# k26_baseboard_connectors1.net
KiCad netlist of a schematic drawn in Altium Designer
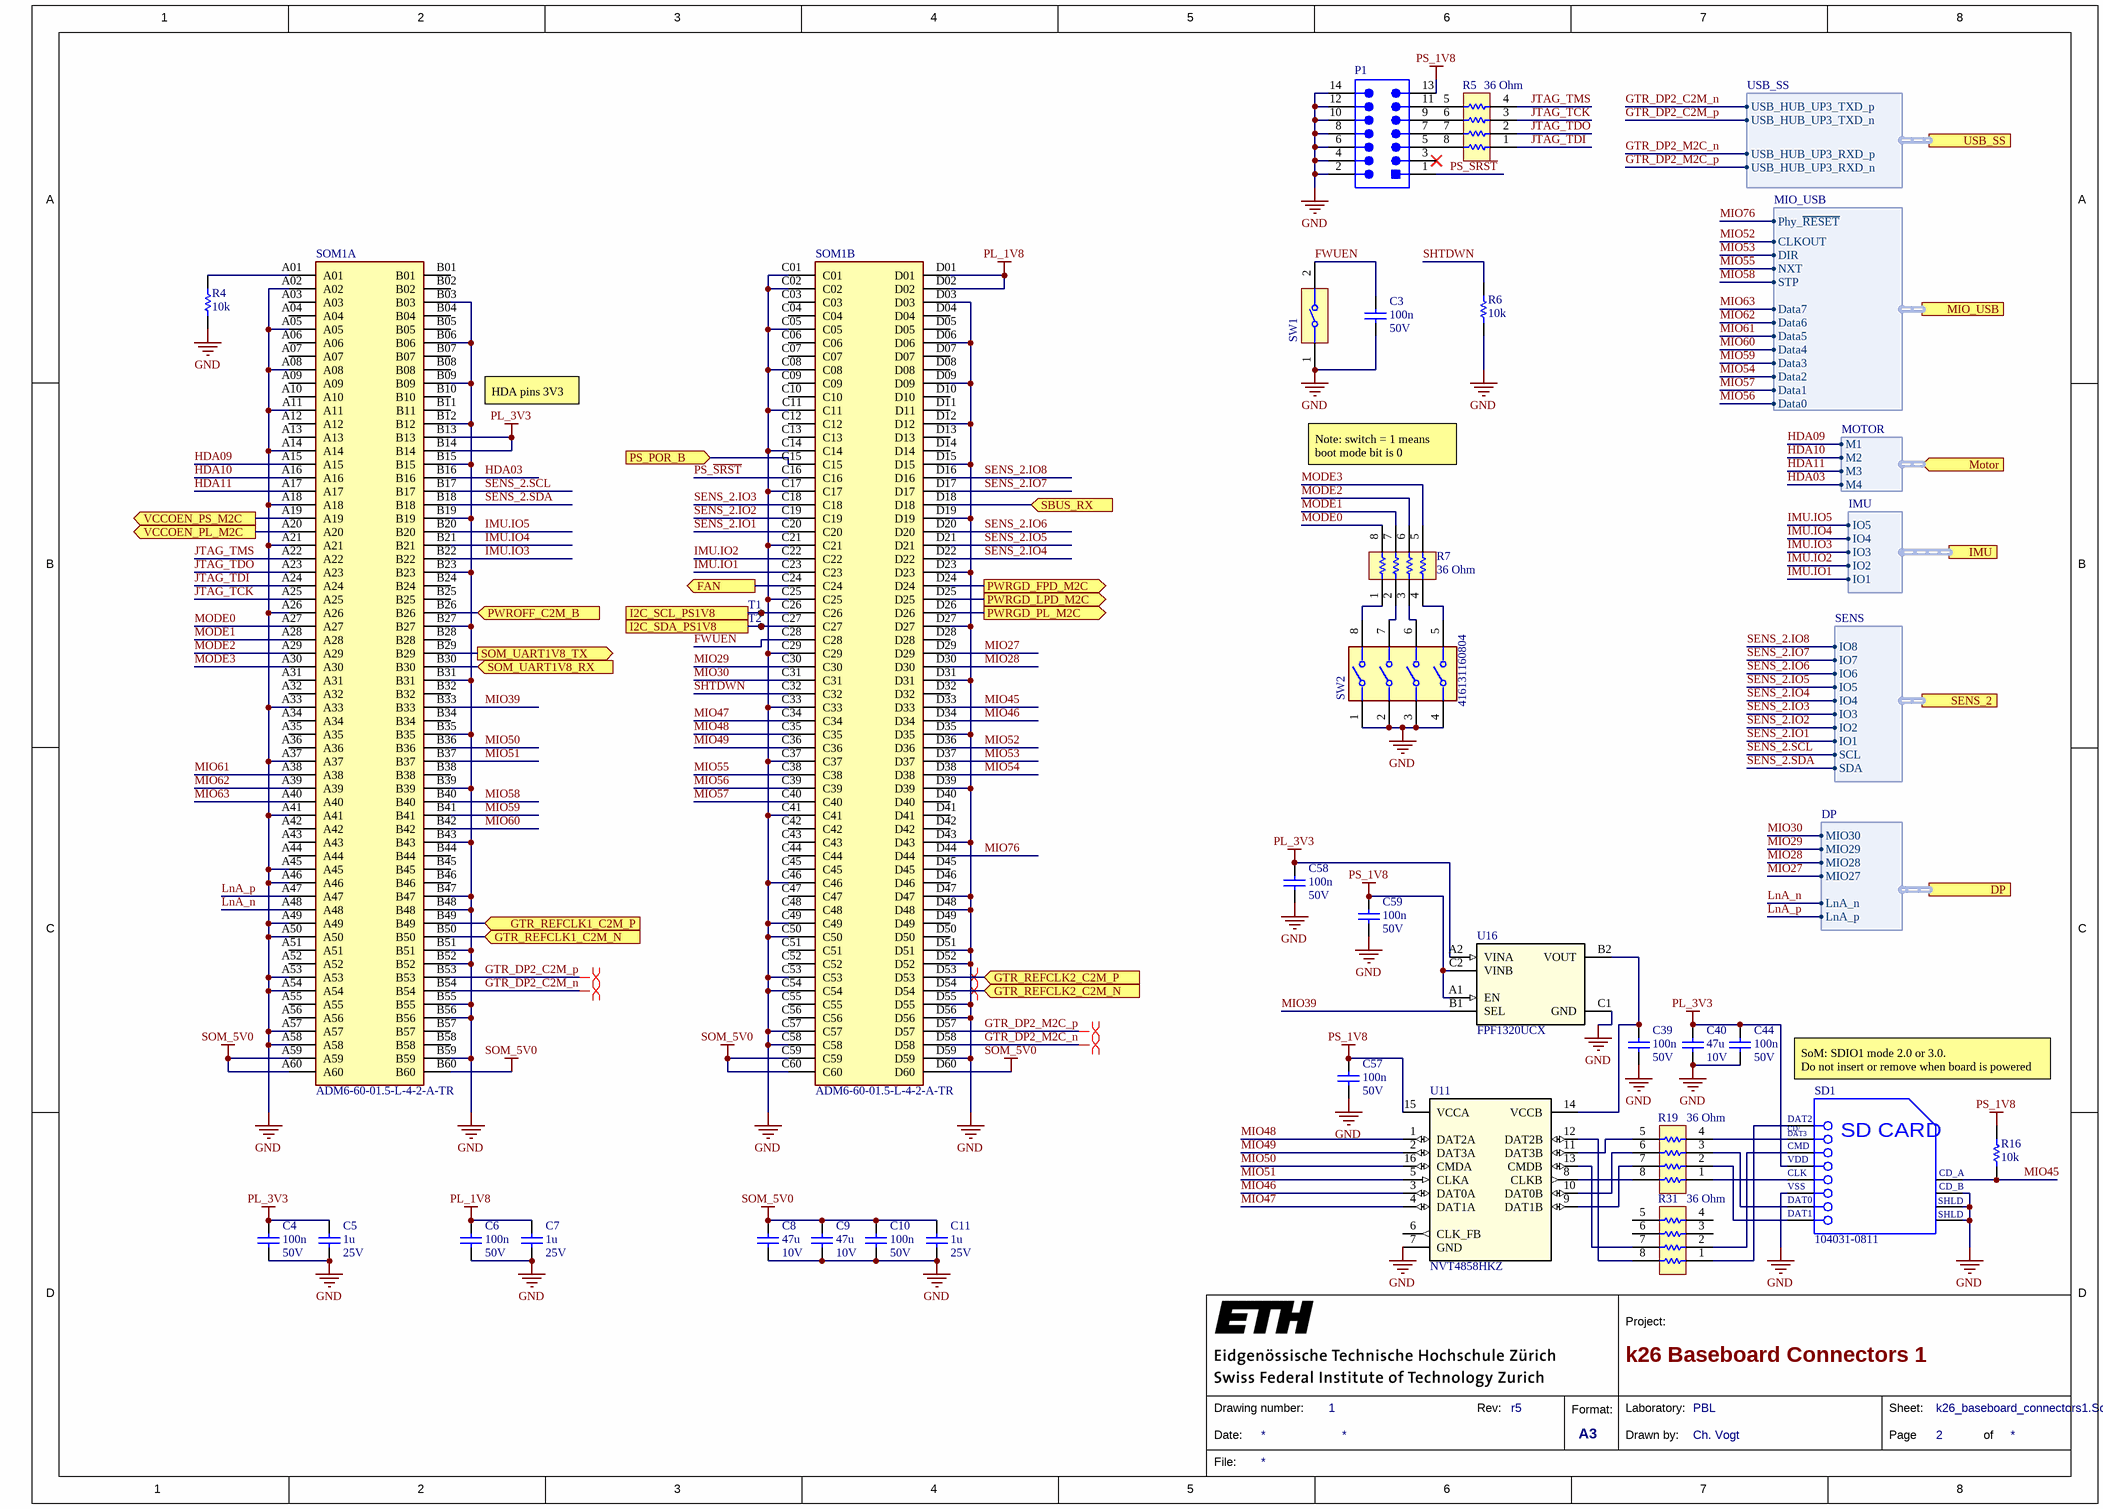
[diagram p0: k26_baseboard_connectors1.SchDoc]

(export (version "E")
  (design (tool "Eeschema 10.0.6"))
  (components
    (comp (ref "C3")
      (value "100n")
      (footprint "k26_FPGA_drone_baseboard:CAPC0402")
      (fields
        (field (name "MANUFACTURER") "Yageo")
        (field (name "MANUFACTURER PART NUMBER") "CC0402KRX5R9BB104")
        (field (name "RATED DC VOLTAGE (URDC)") "50V")
      )
      (libsource (lib "k26_FPGA_drone_baseboard") (part "cap0402"))
    )
    (comp (ref "C4")
      (value "100n")
      (footprint "k26_FPGA_drone_baseboard:CAPC0402")
      (fields
        (field (name "MANUFACTURER") "Yageo")
        (field (name "MANUFACTURER PART NUMBER") "CC0402KRX5R9BB104")
        (field (name "RATED DC VOLTAGE (URDC)") "50V")
      )
      (libsource (lib "k26_FPGA_drone_baseboard") (part "cap0402"))
    )
    (comp (ref "C5")
      (value "1u")
      (footprint "k26_FPGA_drone_baseboard:CAPC0402")
      (fields
        (field (name "MANUFACTURER") "Taiyo Yuden")
        (field (name "MANUFACTURER PART NUMBER") "TMK105BJ105MV-F")
        (field (name "RATED DC VOLTAGE (URDC)") "25V")
      )
      (libsource (lib "k26_FPGA_drone_baseboard") (part "cap0402"))
    )
    (comp (ref "C6")
      (value "100n")
      (footprint "k26_FPGA_drone_baseboard:CAPC0402")
      (fields
        (field (name "MANUFACTURER") "Yageo")
        (field (name "MANUFACTURER PART NUMBER") "CC0402KRX5R9BB104")
        (field (name "RATED DC VOLTAGE (URDC)") "50V")
      )
      (libsource (lib "k26_FPGA_drone_baseboard") (part "cap0402"))
    )
    (comp (ref "C7")
      (value "1u")
      (footprint "k26_FPGA_drone_baseboard:CAPC0402")
      (fields
        (field (name "MANUFACTURER") "Taiyo Yuden")
        (field (name "MANUFACTURER PART NUMBER") "TMK105BJ105MV-F")
        (field (name "RATED DC VOLTAGE (URDC)") "25V")
      )
      (libsource (lib "k26_FPGA_drone_baseboard") (part "cap0402"))
    )
    (comp (ref "C8")
      (value "47u")
      (footprint "k26_FPGA_drone_baseboard:CAPC1206")
      (fields
        (field (name "MANUFACTURER") "KEMET")
        (field (name "MANUFACTURER PART NUMBER") "C1206C476M8PACTU")
        (field (name "RATED DC VOLTAGE (URDC)") "10V")
      )
      (libsource (lib "k26_FPGA_drone_baseboard") (part "cap1206"))
    )
    (comp (ref "C9")
      (value "47u")
      (footprint "k26_FPGA_drone_baseboard:CAPC1206")
      (fields
        (field (name "MANUFACTURER") "KEMET")
        (field (name "MANUFACTURER PART NUMBER") "C1206C476M8PACTU")
        (field (name "RATED DC VOLTAGE (URDC)") "10V")
      )
      (libsource (lib "k26_FPGA_drone_baseboard") (part "cap1206"))
    )
    (comp (ref "C10")
      (value "100n")
      (footprint "k26_FPGA_drone_baseboard:CAPC0402")
      (fields
        (field (name "MANUFACTURER") "Yageo")
        (field (name "MANUFACTURER PART NUMBER") "CC0402KRX5R9BB104")
        (field (name "RATED DC VOLTAGE (URDC)") "50V")
      )
      (libsource (lib "k26_FPGA_drone_baseboard") (part "cap0402"))
    )
    (comp (ref "C11")
      (value "1u")
      (footprint "k26_FPGA_drone_baseboard:CAPC0402")
      (fields
        (field (name "MANUFACTURER") "Taiyo Yuden")
        (field (name "MANUFACTURER PART NUMBER") "TMK105BJ105MV-F")
        (field (name "RATED DC VOLTAGE (URDC)") "25V")
      )
      (libsource (lib "k26_FPGA_drone_baseboard") (part "cap0402"))
    )
    (comp (ref "C39")
      (value "100n")
      (footprint "k26_FPGA_drone_baseboard:CAPC0402")
      (fields
        (field (name "MANUFACTURER") "Yageo")
        (field (name "MANUFACTURER PART NUMBER") "CC0402KRX5R9BB104")
        (field (name "RATED DC VOLTAGE (URDC)") "50V")
      )
      (libsource (lib "k26_FPGA_drone_baseboard") (part "cap0402"))
    )
    (comp (ref "C40")
      (value "47u")
      (footprint "k26_FPGA_drone_baseboard:CAPC1206")
      (fields
        (field (name "MANUFACTURER") "KEMET")
        (field (name "MANUFACTURER PART NUMBER") "C1206C476M8PACTU")
        (field (name "RATED DC VOLTAGE (URDC)") "10V")
      )
      (libsource (lib "k26_FPGA_drone_baseboard") (part "cap1206"))
    )
    (comp (ref "C44")
      (value "100n")
      (footprint "k26_FPGA_drone_baseboard:CAPC0402")
      (fields
        (field (name "MANUFACTURER") "Yageo")
        (field (name "MANUFACTURER PART NUMBER") "CC0402KRX5R9BB104")
        (field (name "RATED DC VOLTAGE (URDC)") "50V")
      )
      (libsource (lib "k26_FPGA_drone_baseboard") (part "cap0402"))
    )
    (comp (ref "C57")
      (value "100n")
      (footprint "k26_FPGA_drone_baseboard:CAPC0402")
      (fields
        (field (name "MANUFACTURER") "Yageo")
        (field (name "MANUFACTURER PART NUMBER") "CC0402KRX5R9BB104")
        (field (name "RATED DC VOLTAGE (URDC)") "50V")
      )
      (libsource (lib "k26_FPGA_drone_baseboard") (part "cap0402"))
    )
    (comp (ref "C58")
      (value "100n")
      (footprint "k26_FPGA_drone_baseboard:CAPC0402")
      (fields
        (field (name "MANUFACTURER") "Yageo")
        (field (name "MANUFACTURER PART NUMBER") "CC0402KRX5R9BB104")
        (field (name "RATED DC VOLTAGE (URDC)") "50V")
      )
      (libsource (lib "k26_FPGA_drone_baseboard") (part "cap0402"))
    )
    (comp (ref "C59")
      (value "100n")
      (footprint "k26_FPGA_drone_baseboard:CAPC0402")
      (fields
        (field (name "MANUFACTURER") "Yageo")
        (field (name "MANUFACTURER PART NUMBER") "CC0402KRX5R9BB104")
        (field (name "RATED DC VOLTAGE (URDC)") "50V")
      )
      (libsource (lib "k26_FPGA_drone_baseboard") (part "cap0402"))
    )
    (comp (ref "P1")
      (value "~")
      (footprint "MOLX-87833-1420_V")
      (description "Male Header, Pitch 2 mm, 2 x 7 Position, Height 6.4 mm, -55 to 105 degC, RoHS, Rail/Tube")
      (fields (field (name "MANUFACTURER") "Molex"))
      (libsource (lib "k26_FPGA_drone_baseboard") (part "CN-2P-M-R14"))
    )
    (comp (ref "R4")
      (value "10k")
      (footprint "k26_FPGA_drone_baseboard:RES0402")
      (fields
        (field (name "MANUFACTURER") "Panasonic")
        (field (name "MANUFACTURER PART NUMBER") "ERJ-2RKF1002X")
        (field (name "TOLERANCE") "1%")
      )
      (libsource (lib "k26_FPGA_drone_baseboard") (part "res0402"))
    )
    (comp (ref "R5")
      (value "CAY10-360J4LF")
      (footprint "BOUR-CAY10-J4_V")
      (description "Chip Resistor Array, 36 Ohm, +/- 5%, 62.5 mW, -55 to 125 degC, 8-Pin SMD, RoHS, Tape and Reel")
      (fields (field (name "RESISTANCE") "36 Ohm") (field (name "TOLERANCE") "5%"))
      (libsource (lib "k26_FPGA_drone_baseboard") (part "RES-P-8"))
    )
    (comp (ref "R6")
      (value "10k")
      (footprint "k26_FPGA_drone_baseboard:RES0402")
      (fields
        (field (name "MANUFACTURER") "Panasonic")
        (field (name "MANUFACTURER PART NUMBER") "ERJ-2RKF1002X")
        (field (name "TOLERANCE") "1%")
      )
      (libsource (lib "k26_FPGA_drone_baseboard") (part "res0402"))
    )
    (comp (ref "R7")
      (value "CAY10-360J4LF")
      (footprint "BOUR-CAY10-J4_V")
      (description "Chip Resistor Array, 36 Ohm, +/- 5%, 62.5 mW, -55 to 125 degC, 8-Pin SMD, RoHS, Tape and Reel")
      (fields (field (name "RESISTANCE") "36 Ohm") (field (name "TOLERANCE") "5%"))
      (libsource (lib "") (part "RES-P-8_1"))
    )
    (comp (ref "R16")
      (value "10k")
      (footprint "k26_FPGA_drone_baseboard:RES0402")
      (fields
        (field (name "MANUFACTURER") "Panasonic")
        (field (name "MANUFACTURER PART NUMBER") "ERJ-2RKF1002X")
        (field (name "TOLERANCE") "1%")
      )
      (libsource (lib "k26_FPGA_drone_baseboard") (part "res0402"))
    )
    (comp (ref "R19")
      (value "CAY10-360J4LF")
      (footprint "BOUR-CAY10-J4_V")
      (description "Chip Resistor Array, 36 Ohm, +/- 5%, 62.5 mW, -55 to 125 degC, 8-Pin SMD, RoHS, Tape and Reel")
      (fields (field (name "RESISTANCE") "36 Ohm") (field (name "TOLERANCE") "5%"))
      (libsource (lib "k26_FPGA_drone_baseboard") (part "RES-P-8"))
    )
    (comp (ref "R31")
      (value "CAY10-360J4LF")
      (footprint "BOUR-CAY10-J4_V")
      (description "Chip Resistor Array, 36 Ohm, +/- 5%, 62.5 mW, -55 to 125 degC, 8-Pin SMD, RoHS, Tape and Reel")
      (fields (field (name "RESISTANCE") "36 Ohm") (field (name "TOLERANCE") "5%"))
      (libsource (lib "k26_FPGA_drone_baseboard") (part "RES-P-8"))
    )
    (comp (ref "SD1")
      (value "104031-0811")
      (footprint "MOLX-104031-0811_V")
      (description "Micro SD Card, RA, -25 to 85 degC, 8-Pin SMD, RoHS, Tape and Reel")
      (fields (field (name "MANUFACTURER") "Molex") (field (name "MANUFACTURER PART NUMBER") "1040310811"))
      (libsource (lib "k26_FPGA_drone_baseboard") (part "CMP-2000-05825-1"))
    )
    (comp (ref "SOM1")
      (value "ADM6-60-01.5-L-4-2-A-TR")
      (footprint "k26_FPGA_drone_baseboard:SAMTEC_ADM6-60-01.5-L-4-2-A-TR")
      (description "0.635 mm AcceleRate HD High-Density 4-Row Header")
      (libsource (lib "k26_FPGA_drone_baseboard") (part "ADM6-60-01.5-L-4-2-A-TR"))
    )
    (comp (ref "SW1")
      (value "KSS241GLFS")
      (footprint "KSS241GLFS")
      (description "SWITCH TACTILE SPST-NO 0.05A 50V")
      (fields (field (name "MANUFACTURER") "ITT C&K"))
      (libsource (lib "k26_FPGA_drone_baseboard") (part "CMP-00077-3"))
    )
    (comp (ref "SW2")
      (value "416131160804")
      (footprint "FP-416131160804-MFG")
      (description "SWITCH SLIDE DIP SPST 25MA 24V")
      (libsource (lib "k26_FPGA_drone_baseboard") (part "c3c4c2ac9515373cfee496e575704c1"))
    )
    (comp (ref "T1")
      (value "~")
      (footprint "Pad-1mm")
      (description "1mm SMT Test Pad")
      (libsource (lib "k26_FPGA_drone_baseboard") (part "Test Pad"))
    )
    (comp (ref "T2")
      (value "~")
      (footprint "Pad-1mm")
      (description "1mm SMT Test Pad")
      (libsource (lib "k26_FPGA_drone_baseboard") (part "Test Pad"))
    )
    (comp (ref "U11")
      (value "NVT4858HKZ")
      (footprint "NVT4858_NXP")
      (description "No Description Available")
      (libsource (lib "k26_FPGA_drone_baseboard") (part "NVT4858HKZ"))
    )
    (comp (ref "U16")
      (value "FPF1320UCX")
      (footprint "WLCSP6_1X1.5_ONS-M")
      (description "No Description Available")
      (libsource (lib "k26_FPGA_drone_baseboard") (part "FPF1320UCX"))
    )
  )
  (nets
    (net (code "7") (name "/FAN") (class "Default")
      (node (ref "SOM1") (pin "C24") (pinfunction "C24_C24") (pintype "passive"))
    )
    (net (code "8") (name "/FWUEN") (class "Default")
      (node (ref "C3") (pin "2") (pinfunction "2_2") (pintype "passive"))
      (node (ref "SOM1") (pin "C28") (pinfunction "C28_C28") (pintype "passive"))
      (node (ref "SW1") (pin "2") (pinfunction "T2_2") (pintype "passive"))
    )
    (net (code "9") (name "/GTR_DP2_C2M_n") (class "Default")
      (node (ref "SOM1") (pin "B54") (pinfunction "B54_B54") (pintype "passive"))
    )
    (net (code "10") (name "/GTR_DP2_C2M_p") (class "Default")
      (node (ref "SOM1") (pin "B53") (pinfunction "B53_B53") (pintype "passive"))
    )
    (net (code "11") (name "/GTR_DP2_M2C_n") (class "Default")
      (node (ref "SOM1") (pin "D58") (pinfunction "D58_D58") (pintype "passive"))
    )
    (net (code "12") (name "/GTR_DP2_M2C_p") (class "Default")
      (node (ref "SOM1") (pin "D57") (pinfunction "D57_D57") (pintype "passive"))
    )
    (net (code "13") (name "/GTR_REFCLK1_C2M_N") (class "Default")
      (node (ref "SOM1") (pin "B50") (pinfunction "B50_B50") (pintype "passive"))
    )
    (net (code "14") (name "/GTR_REFCLK1_C2M_P") (class "Default")
      (node (ref "SOM1") (pin "B49") (pinfunction "B49_B49") (pintype "passive"))
    )
    (net (code "15") (name "/GTR_REFCLK2_C2M_N") (class "Default")
      (node (ref "SOM1") (pin "D54") (pinfunction "D54_D54") (pintype "passive"))
    )
    (net (code "16") (name "/GTR_REFCLK2_C2M_P") (class "Default")
      (node (ref "SOM1") (pin "D53") (pinfunction "D53_D53") (pintype "passive"))
    )
    (net (code "17") (name "/HDA03") (class "Default")
      (node (ref "SOM1") (pin "B16") (pinfunction "B16_B16") (pintype "passive"))
    )
    (net (code "18") (name "/HDA09") (class "Default")
      (node (ref "SOM1") (pin "A15") (pinfunction "A15_A15") (pintype "passive"))
    )
    (net (code "19") (name "/HDA10") (class "Default")
      (node (ref "SOM1") (pin "A16") (pinfunction "A16_A16") (pintype "passive"))
    )
    (net (code "20") (name "/HDA11") (class "Default")
      (node (ref "SOM1") (pin "A17") (pinfunction "A17_A17") (pintype "passive"))
    )
    (net (code "21") (name "/I2C_SCL_PS1V8") (class "Default")
      (node (ref "SOM1") (pin "C26") (pinfunction "C26_C26") (pintype "passive"))
      (node (ref "T1") (pin "1") (pinfunction "1_1") (pintype "passive"))
    )
    (net (code "22") (name "/I2C_SDA_PS1V8") (class "Default")
      (node (ref "SOM1") (pin "C27") (pinfunction "C27_C27") (pintype "passive"))
      (node (ref "T2") (pin "1") (pinfunction "1_1") (pintype "passive"))
    )
    (net (code "23") (name "/IMU.IO1") (class "Default")
      (node (ref "SOM1") (pin "C23") (pinfunction "C23_C23") (pintype "passive"))
    )
    (net (code "24") (name "/IMU.IO2") (class "Default")
      (node (ref "SOM1") (pin "C22") (pinfunction "C22_C22") (pintype "passive"))
    )
    (net (code "25") (name "/IMU.IO3") (class "Default")
      (node (ref "SOM1") (pin "B22") (pinfunction "B22_B22") (pintype "passive"))
    )
    (net (code "26") (name "/IMU.IO4") (class "Default")
      (node (ref "SOM1") (pin "B21") (pinfunction "B21_B21") (pintype "passive"))
    )
    (net (code "27") (name "/IMU.IO5") (class "Default")
      (node (ref "SOM1") (pin "B20") (pinfunction "B20_B20") (pintype "passive"))
    )
    (net (code "28") (name "/JTAG_TCK") (class "Default")
      (node (ref "R5") (pin "3") (pinfunction "3_3") (pintype "passive"))
      (node (ref "SOM1") (pin "A25") (pinfunction "A25_A25") (pintype "passive"))
    )
    (net (code "29") (name "/JTAG_TDI") (class "Default")
      (node (ref "R5") (pin "1") (pinfunction "1_1") (pintype "passive"))
      (node (ref "SOM1") (pin "A24") (pinfunction "A24_A24") (pintype "passive"))
    )
    (net (code "30") (name "/JTAG_TDO") (class "Default")
      (node (ref "R5") (pin "2") (pinfunction "2_2") (pintype "passive"))
      (node (ref "SOM1") (pin "A23") (pinfunction "A23_A23") (pintype "passive"))
    )
    (net (code "31") (name "/JTAG_TMS") (class "Default")
      (node (ref "R5") (pin "4") (pinfunction "4_4") (pintype "passive"))
      (node (ref "SOM1") (pin "A22") (pinfunction "A22_A22") (pintype "passive"))
    )
    (net (code "32") (name "/LnA_n") (class "Default")
      (node (ref "SOM1") (pin "A48") (pinfunction "A48_A48") (pintype "passive"))
    )
    (net (code "33") (name "/LnA_p") (class "Default")
      (node (ref "SOM1") (pin "A47") (pinfunction "A47_A47") (pintype "passive"))
    )
    (net (code "34") (name "/MIO27") (class "Default")
      (node (ref "SOM1") (pin "D29") (pinfunction "D29_D29") (pintype "passive"))
    )
    (net (code "35") (name "/MIO28") (class "Default")
      (node (ref "SOM1") (pin "D30") (pinfunction "D30_D30") (pintype "passive"))
    )
    (net (code "36") (name "/MIO29") (class "Default")
      (node (ref "SOM1") (pin "C30") (pinfunction "C30_C30") (pintype "passive"))
    )
    (net (code "37") (name "/MIO30") (class "Default")
      (node (ref "SOM1") (pin "C31") (pinfunction "C31_C31") (pintype "passive"))
    )
    (net (code "38") (name "/MIO39") (class "Default")
      (node (ref "SOM1") (pin "B33") (pinfunction "B33_B33") (pintype "passive"))
      (node (ref "U16") (pin "B1") (pinfunction "SEL_B1") (pintype "power_in"))
    )
    (net (code "39") (name "/MIO45") (class "Default")
      (node (ref "R16") (pin "1") (pinfunction "1_1") (pintype "passive"))
      (node (ref "SD1") (pin "9") (pinfunction "CD_A_9") (pintype "passive"))
      (node (ref "SOM1") (pin "D33") (pinfunction "D33_D33") (pintype "passive"))
    )
    (net (code "40") (name "/MIO46") (class "Default")
      (node (ref "SOM1") (pin "D34") (pinfunction "D34_D34") (pintype "passive"))
      (node (ref "U11") (pin "3") (pinfunction "DAT0A_3") (pintype "bidirectional"))
    )
    (net (code "41") (name "/MIO47") (class "Default")
      (node (ref "SOM1") (pin "C34") (pinfunction "C34_C34") (pintype "passive"))
      (node (ref "U11") (pin "4") (pinfunction "DAT1A_4") (pintype "bidirectional"))
    )
    (net (code "42") (name "/MIO48") (class "Default")
      (node (ref "SOM1") (pin "C35") (pinfunction "C35_C35") (pintype "passive"))
      (node (ref "U11") (pin "1") (pinfunction "DAT2A_1") (pintype "bidirectional"))
    )
    (net (code "43") (name "/MIO49") (class "Default")
      (node (ref "SOM1") (pin "C36") (pinfunction "C36_C36") (pintype "passive"))
      (node (ref "U11") (pin "2") (pinfunction "DAT3A_2") (pintype "bidirectional"))
    )
    (net (code "44") (name "/MIO50") (class "Default")
      (node (ref "SOM1") (pin "B36") (pinfunction "B36_B36") (pintype "passive"))
      (node (ref "U11") (pin "16") (pinfunction "CMDA_16") (pintype "bidirectional"))
    )
    (net (code "45") (name "/MIO51") (class "Default")
      (node (ref "SOM1") (pin "B37") (pinfunction "B37_B37") (pintype "passive"))
      (node (ref "U11") (pin "5") (pinfunction "CLKA_5") (pintype "input"))
    )
    (net (code "46") (name "/MIO52") (class "Default")
      (node (ref "SOM1") (pin "D36") (pinfunction "D36_D36") (pintype "passive"))
    )
    (net (code "47") (name "/MIO53") (class "Default")
      (node (ref "SOM1") (pin "D37") (pinfunction "D37_D37") (pintype "passive"))
    )
    (net (code "48") (name "/MIO54") (class "Default")
      (node (ref "SOM1") (pin "D38") (pinfunction "D38_D38") (pintype "passive"))
    )
    (net (code "49") (name "/MIO55") (class "Default")
      (node (ref "SOM1") (pin "C38") (pinfunction "C38_C38") (pintype "passive"))
    )
    (net (code "50") (name "/MIO56") (class "Default")
      (node (ref "SOM1") (pin "C39") (pinfunction "C39_C39") (pintype "passive"))
    )
    (net (code "51") (name "/MIO57") (class "Default")
      (node (ref "SOM1") (pin "C40") (pinfunction "C40_C40") (pintype "passive"))
    )
    (net (code "52") (name "/MIO58") (class "Default")
      (node (ref "SOM1") (pin "B40") (pinfunction "B40_B40") (pintype "passive"))
    )
    (net (code "53") (name "/MIO59") (class "Default")
      (node (ref "SOM1") (pin "B41") (pinfunction "B41_B41") (pintype "passive"))
    )
    (net (code "54") (name "/MIO60") (class "Default")
      (node (ref "SOM1") (pin "B42") (pinfunction "B42_B42") (pintype "passive"))
    )
    (net (code "55") (name "/MIO61") (class "Default")
      (node (ref "SOM1") (pin "A38") (pinfunction "A38_A38") (pintype "passive"))
    )
    (net (code "56") (name "/MIO62") (class "Default")
      (node (ref "SOM1") (pin "A39") (pinfunction "A39_A39") (pintype "passive"))
    )
    (net (code "57") (name "/MIO63") (class "Default")
      (node (ref "SOM1") (pin "A40") (pinfunction "A40_A40") (pintype "passive"))
    )
    (net (code "58") (name "/MIO76") (class "Default")
      (node (ref "SOM1") (pin "D44") (pinfunction "D44_D44") (pintype "passive"))
    )
    (net (code "59") (name "/MODE0") (class "Default")
      (node (ref "R7") (pin "8") (pinfunction "8_8") (pintype "passive"))
      (node (ref "SOM1") (pin "A27") (pinfunction "A27_A27") (pintype "passive"))
    )
    (net (code "60") (name "/MODE1") (class "Default")
      (node (ref "R7") (pin "7") (pinfunction "7_7") (pintype "passive"))
      (node (ref "SOM1") (pin "A28") (pinfunction "A28_A28") (pintype "passive"))
    )
    (net (code "61") (name "/MODE2") (class "Default")
      (node (ref "R7") (pin "6") (pinfunction "6_6") (pintype "passive"))
      (node (ref "SOM1") (pin "A29") (pinfunction "A29_A29") (pintype "passive"))
    )
    (net (code "62") (name "/MODE3") (class "Default")
      (node (ref "R7") (pin "5") (pinfunction "5_5") (pintype "passive"))
      (node (ref "SOM1") (pin "A30") (pinfunction "A30_A30") (pintype "passive"))
    )
    (net (code "63") (name "/PS_POR_B") (class "Default")
      (node (ref "SOM1") (pin "C15") (pinfunction "C15_C15") (pintype "passive"))
    )
    (net (code "64") (name "/PS_~{SRST}") (class "Default")
      (node (ref "P1") (pin "1") (pinfunction "1_1") (pintype "passive"))
      (node (ref "SOM1") (pin "C16") (pinfunction "C16_C16") (pintype "passive"))
    )
    (net (code "65") (name "/PWRGD_FPD_M2C") (class "Default")
      (node (ref "SOM1") (pin "D24") (pinfunction "D24_D24") (pintype "passive"))
    )
    (net (code "66") (name "/PWRGD_LPD_M2C") (class "Default")
      (node (ref "SOM1") (pin "D25") (pinfunction "D25_D25") (pintype "passive"))
    )
    (net (code "67") (name "/PWRGD_PL_M2C") (class "Default")
      (node (ref "SOM1") (pin "D26") (pinfunction "D26_D26") (pintype "passive"))
    )
    (net (code "68") (name "/PWROFF_C2M_B") (class "Default")
      (node (ref "SOM1") (pin "B26") (pinfunction "B26_B26") (pintype "passive"))
    )
    (net (code "69") (name "/SBUS_RX") (class "Default")
      (node (ref "SOM1") (pin "D18") (pinfunction "D18_D18") (pintype "passive"))
    )
    (net (code "70") (name "/SENS_2.IO1") (class "Default")
      (node (ref "SOM1") (pin "C20") (pinfunction "C20_C20") (pintype "passive"))
    )
    (net (code "71") (name "/SENS_2.IO2") (class "Default")
      (node (ref "SOM1") (pin "C19") (pinfunction "C19_C19") (pintype "passive"))
    )
    (net (code "72") (name "/SENS_2.IO3") (class "Default")
      (node (ref "SOM1") (pin "C18") (pinfunction "C18_C18") (pintype "passive"))
    )
    (net (code "73") (name "/SENS_2.IO4") (class "Default")
      (node (ref "SOM1") (pin "D22") (pinfunction "D22_D22") (pintype "passive"))
    )
    (net (code "74") (name "/SENS_2.IO5") (class "Default")
      (node (ref "SOM1") (pin "D21") (pinfunction "D21_D21") (pintype "passive"))
    )
    (net (code "75") (name "/SENS_2.IO6") (class "Default")
      (node (ref "SOM1") (pin "D20") (pinfunction "D20_D20") (pintype "passive"))
    )
    (net (code "76") (name "/SENS_2.IO7") (class "Default")
      (node (ref "SOM1") (pin "D17") (pinfunction "D17_D17") (pintype "passive"))
    )
    (net (code "77") (name "/SENS_2.IO8") (class "Default")
      (node (ref "SOM1") (pin "D16") (pinfunction "D16_D16") (pintype "passive"))
    )
    (net (code "78") (name "/SENS_2.SCL") (class "Default")
      (node (ref "SOM1") (pin "B17") (pinfunction "B17_B17") (pintype "passive"))
    )
    (net (code "79") (name "/SENS_2.SDA") (class "Default")
      (node (ref "SOM1") (pin "B18") (pinfunction "B18_B18") (pintype "passive"))
    )
    (net (code "80") (name "/SHTDWN") (class "Default")
      (node (ref "R6") (pin "2") (pinfunction "2_2") (pintype "passive"))
      (node (ref "SOM1") (pin "C32") (pinfunction "C32_C32") (pintype "passive"))
    )
    (net (code "81") (name "/SOM_UART1V8_RX") (class "Default")
      (node (ref "SOM1") (pin "B30") (pinfunction "B30_B30") (pintype "passive"))
    )
    (net (code "82") (name "/SOM_UART1V8_TX") (class "Default")
      (node (ref "SOM1") (pin "B29") (pinfunction "B29_B29") (pintype "passive"))
    )
    (net (code "83") (name "/VCCOEN_PL_M2C") (class "Default")
      (node (ref "SOM1") (pin "A20") (pinfunction "A20_A20") (pintype "passive"))
    )
    (net (code "84") (name "/VCCOEN_PS_M2C") (class "Default")
      (node (ref "SOM1") (pin "A19") (pinfunction "A19_A19") (pintype "passive"))
    )
    (net (code "91") (name "GND") (class "Default")
      (node (ref "C10") (pin "1") (pinfunction "1_1") (pintype "passive"))
      (node (ref "C11") (pin "1") (pinfunction "1_1") (pintype "passive"))
      (node (ref "C3") (pin "1") (pinfunction "1_1") (pintype "passive"))
      (node (ref "C39") (pin "1") (pinfunction "1_1") (pintype "passive"))
      (node (ref "C4") (pin "1") (pinfunction "1_1") (pintype "passive"))
      (node (ref "C40") (pin "1") (pinfunction "1_1") (pintype "passive"))
      (node (ref "C44") (pin "1") (pinfunction "1_1") (pintype "passive"))
      (node (ref "C5") (pin "1") (pinfunction "1_1") (pintype "passive"))
      (node (ref "C57") (pin "1") (pinfunction "1_1") (pintype "passive"))
      (node (ref "C58") (pin "1") (pinfunction "1_1") (pintype "passive"))
      (node (ref "C59") (pin "1") (pinfunction "1_1") (pintype "passive"))
      (node (ref "C6") (pin "1") (pinfunction "1_1") (pintype "passive"))
      (node (ref "C7") (pin "1") (pinfunction "1_1") (pintype "passive"))
      (node (ref "C8") (pin "1") (pinfunction "1_1") (pintype "passive"))
      (node (ref "C9") (pin "1") (pinfunction "1_1") (pintype "passive"))
      (node (ref "P1") (pin "10") (pinfunction "10_10") (pintype "passive"))
      (node (ref "P1") (pin "12") (pinfunction "12_12") (pintype "passive"))
      (node (ref "P1") (pin "14") (pinfunction "14_14") (pintype "passive"))
      (node (ref "P1") (pin "2") (pinfunction "2_2") (pintype "passive"))
      (node (ref "P1") (pin "4") (pinfunction "4_4") (pintype "passive"))
      (node (ref "P1") (pin "6") (pinfunction "6_6") (pintype "passive"))
      (node (ref "P1") (pin "8") (pinfunction "8_8") (pintype "passive"))
      (node (ref "R4") (pin "1") (pinfunction "1_1") (pintype "passive"))
      (node (ref "R6") (pin "1") (pinfunction "1_1") (pintype "passive"))
      (node (ref "SD1") (pin "10") (pinfunction "CD_B_10") (pintype "passive"))
      (node (ref "SD1") (pin "11") (pinfunction "SHLD1_11") (pintype "passive"))
      (node (ref "SD1") (pin "12") (pinfunction "SHLD2_12") (pintype "passive"))
      (node (ref "SD1") (pin "6") (pinfunction "VSS2_6") (pintype "passive"))
      (node (ref "SOM1") (pin "A02") (pinfunction "A02_A02") (pintype "passive"))
      (node (ref "SOM1") (pin "A05") (pinfunction "A05_A05") (pintype "passive"))
      (node (ref "SOM1") (pin "A08") (pinfunction "A08_A08") (pintype "passive"))
      (node (ref "SOM1") (pin "A11") (pinfunction "A11_A11") (pintype "passive"))
      (node (ref "SOM1") (pin "A14") (pinfunction "A14_A14") (pintype "passive"))
      (node (ref "SOM1") (pin "A18") (pinfunction "A18_A18") (pintype "passive"))
      (node (ref "SOM1") (pin "A21") (pinfunction "A21_A21") (pintype "passive"))
      (node (ref "SOM1") (pin "A26") (pinfunction "A26_A26") (pintype "passive"))
      (node (ref "SOM1") (pin "A33") (pinfunction "A33_A33") (pintype "passive"))
      (node (ref "SOM1") (pin "A37") (pinfunction "A37_A37") (pintype "passive"))
      (node (ref "SOM1") (pin "A41") (pinfunction "A41_A41") (pintype "passive"))
      (node (ref "SOM1") (pin "A45") (pinfunction "A45_A45") (pintype "passive"))
      (node (ref "SOM1") (pin "A46") (pinfunction "A46_A46") (pintype "passive"))
      (node (ref "SOM1") (pin "A49") (pinfunction "A49_A49") (pintype "passive"))
      (node (ref "SOM1") (pin "A50") (pinfunction "A50_A50") (pintype "passive"))
      (node (ref "SOM1") (pin "A53") (pinfunction "A53_A53") (pintype "passive"))
      (node (ref "SOM1") (pin "A54") (pinfunction "A54_A54") (pintype "passive"))
      (node (ref "SOM1") (pin "A57") (pinfunction "A57_A57") (pintype "passive"))
      (node (ref "SOM1") (pin "A58") (pinfunction "A58_A58") (pintype "passive"))
      (node (ref "SOM1") (pin "B03") (pinfunction "B03_B03") (pintype "passive"))
      (node (ref "SOM1") (pin "B06") (pinfunction "B06_B06") (pintype "passive"))
      (node (ref "SOM1") (pin "B09") (pinfunction "B09_B09") (pintype "passive"))
      (node (ref "SOM1") (pin "B12") (pinfunction "B12_B12") (pintype "passive"))
      (node (ref "SOM1") (pin "B15") (pinfunction "B15_B15") (pintype "passive"))
      (node (ref "SOM1") (pin "B19") (pinfunction "B19_B19") (pintype "passive"))
      (node (ref "SOM1") (pin "B23") (pinfunction "B23_B23") (pintype "passive"))
      (node (ref "SOM1") (pin "B27") (pinfunction "B27_B27") (pintype "passive"))
      (node (ref "SOM1") (pin "B31") (pinfunction "B31_B31") (pintype "passive"))
      (node (ref "SOM1") (pin "B35") (pinfunction "B35_B35") (pintype "passive"))
      (node (ref "SOM1") (pin "B39") (pinfunction "B39_B39") (pintype "passive"))
      (node (ref "SOM1") (pin "B43") (pinfunction "B43_B43") (pintype "passive"))
      (node (ref "SOM1") (pin "B47") (pinfunction "B47_B47") (pintype "passive"))
      (node (ref "SOM1") (pin "B48") (pinfunction "B48_B48") (pintype "passive"))
      (node (ref "SOM1") (pin "B51") (pinfunction "B51_B51") (pintype "passive"))
      (node (ref "SOM1") (pin "B52") (pinfunction "B52_B52") (pintype "passive"))
      (node (ref "SOM1") (pin "B55") (pinfunction "B55_B55") (pintype "passive"))
      (node (ref "SOM1") (pin "B56") (pinfunction "B56_B56") (pintype "passive"))
      (node (ref "SOM1") (pin "B59") (pinfunction "B59_B59") (pintype "passive"))
      (node (ref "SOM1") (pin "C01") (pinfunction "C01_C01") (pintype "passive"))
      (node (ref "SOM1") (pin "C02") (pinfunction "C02_C02") (pintype "passive"))
      (node (ref "SOM1") (pin "C05") (pinfunction "C05_C05") (pintype "passive"))
      (node (ref "SOM1") (pin "C08") (pinfunction "C08_C08") (pintype "passive"))
      (node (ref "SOM1") (pin "C11") (pinfunction "C11_C11") (pintype "passive"))
      (node (ref "SOM1") (pin "C14") (pinfunction "C14_C14") (pintype "passive"))
      (node (ref "SOM1") (pin "C17") (pinfunction "C17_C17") (pintype "passive"))
      (node (ref "SOM1") (pin "C21") (pinfunction "C21_C21") (pintype "passive"))
      (node (ref "SOM1") (pin "C25") (pinfunction "C25_C25") (pintype "passive"))
      (node (ref "SOM1") (pin "C29") (pinfunction "C29_C29") (pintype "passive"))
      (node (ref "SOM1") (pin "C33") (pinfunction "C33_C33") (pintype "passive"))
      (node (ref "SOM1") (pin "C37") (pinfunction "C37_C37") (pintype "passive"))
      (node (ref "SOM1") (pin "C41") (pinfunction "C41_C41") (pintype "passive"))
      (node (ref "SOM1") (pin "C46") (pinfunction "C46_C46") (pintype "passive"))
      (node (ref "SOM1") (pin "C49") (pinfunction "C49_C49") (pintype "passive"))
      (node (ref "SOM1") (pin "C50") (pinfunction "C50_C50") (pintype "passive"))
      (node (ref "SOM1") (pin "C53") (pinfunction "C53_C53") (pintype "passive"))
      (node (ref "SOM1") (pin "C54") (pinfunction "C54_C54") (pintype "passive"))
      (node (ref "SOM1") (pin "C57") (pinfunction "C57_C57") (pintype "passive"))
      (node (ref "SOM1") (pin "C58") (pinfunction "C58_C58") (pintype "passive"))
      (node (ref "SOM1") (pin "D03") (pinfunction "D03_D03") (pintype "passive"))
      (node (ref "SOM1") (pin "D06") (pinfunction "D06_D06") (pintype "passive"))
      (node (ref "SOM1") (pin "D09") (pinfunction "D09_D09") (pintype "passive"))
      (node (ref "SOM1") (pin "D12") (pinfunction "D12_D12") (pintype "passive"))
      (node (ref "SOM1") (pin "D15") (pinfunction "D15_D15") (pintype "passive"))
      (node (ref "SOM1") (pin "D19") (pinfunction "D19_D19") (pintype "passive"))
      (node (ref "SOM1") (pin "D23") (pinfunction "D23_D23") (pintype "passive"))
      (node (ref "SOM1") (pin "D27") (pinfunction "D27_D27") (pintype "passive"))
      (node (ref "SOM1") (pin "D31") (pinfunction "D31_D31") (pintype "passive"))
      (node (ref "SOM1") (pin "D35") (pinfunction "D35_D35") (pintype "passive"))
      (node (ref "SOM1") (pin "D39") (pinfunction "D39_D39") (pintype "passive"))
      (node (ref "SOM1") (pin "D43") (pinfunction "D43_D43") (pintype "passive"))
      (node (ref "SOM1") (pin "D47") (pinfunction "D47_D47") (pintype "passive"))
      (node (ref "SOM1") (pin "D48") (pinfunction "D48_D48") (pintype "passive"))
      (node (ref "SOM1") (pin "D51") (pinfunction "D51_D51") (pintype "passive"))
      (node (ref "SOM1") (pin "D52") (pinfunction "D52_D52") (pintype "passive"))
      (node (ref "SOM1") (pin "D55") (pinfunction "D55_D55") (pintype "passive"))
      (node (ref "SOM1") (pin "D56") (pinfunction "D56_D56") (pintype "passive"))
      (node (ref "SOM1") (pin "D59") (pinfunction "D59_D59") (pintype "passive"))
      (node (ref "SW1") (pin "1") (pinfunction "T1_1") (pintype "passive"))
      (node (ref "SW2") (pin "1") (pinfunction "1_1") (pintype "passive"))
      (node (ref "SW2") (pin "2") (pinfunction "2_2") (pintype "passive"))
      (node (ref "SW2") (pin "3") (pinfunction "3_3") (pintype "passive"))
      (node (ref "SW2") (pin "4") (pinfunction "4_4") (pintype "passive"))
      (node (ref "U11") (pin "7") (pinfunction "GND_7") (pintype "power_in"))
      (node (ref "U16") (pin "C1") (pinfunction "GND_C1") (pintype "power_in"))
    )
    (net (code "92") (name "Net-(P1-Pad5)") (class "Default")
      (node (ref "P1") (pin "5") (pinfunction "5_5") (pintype "passive"))
      (node (ref "R5") (pin "8") (pinfunction "8_8") (pintype "passive"))
    )
    (net (code "93") (name "Net-(P1-Pad7)") (class "Default")
      (node (ref "P1") (pin "7") (pinfunction "7_7") (pintype "passive"))
      (node (ref "R5") (pin "7") (pinfunction "7_7") (pintype "passive"))
    )
    (net (code "94") (name "Net-(P1-Pad9)") (class "Default")
      (node (ref "P1") (pin "9") (pinfunction "9_9") (pintype "passive"))
      (node (ref "R5") (pin "6") (pinfunction "6_6") (pintype "passive"))
    )
    (net (code "95") (name "Net-(P1-Pad11)") (class "Default")
      (node (ref "P1") (pin "11") (pinfunction "11_11") (pintype "passive"))
      (node (ref "R5") (pin "5") (pinfunction "5_5") (pintype "passive"))
    )
    (net (code "96") (name "Net-(R4-Pad2)") (class "Default")
      (node (ref "R4") (pin "2") (pinfunction "2_2") (pintype "passive"))
      (node (ref "SOM1") (pin "A01") (pinfunction "A01_A01") (pintype "passive"))
    )
    (net (code "97") (name "Net-(R7-Pad1)") (class "Default")
      (node (ref "R7") (pin "1") (pinfunction "1_1") (pintype "passive"))
      (node (ref "SW2") (pin "8") (pinfunction "8_8") (pintype "passive"))
    )
    (net (code "98") (name "Net-(R7-Pad2)") (class "Default")
      (node (ref "R7") (pin "2") (pinfunction "2_2") (pintype "passive"))
      (node (ref "SW2") (pin "7") (pinfunction "7_7") (pintype "passive"))
    )
    (net (code "99") (name "Net-(R7-Pad3)") (class "Default")
      (node (ref "R7") (pin "3") (pinfunction "3_3") (pintype "passive"))
      (node (ref "SW2") (pin "6") (pinfunction "6_6") (pintype "passive"))
    )
    (net (code "100") (name "Net-(R7-Pad4)") (class "Default")
      (node (ref "R7") (pin "4") (pinfunction "4_4") (pintype "passive"))
      (node (ref "SW2") (pin "5") (pinfunction "5_5") (pintype "passive"))
    )
    (net (code "101") (name "Net-(SD1-CD{slash}DAT3)") (class "Default")
      (node (ref "R31") (pin "1") (pinfunction "1_1") (pintype "passive"))
      (node (ref "SD1") (pin "1") (pinfunction "CD/DAT3_1") (pintype "passive"))
    )
    (net (code "102") (name "Net-(SD1-CLK)") (class "Default")
      (node (ref "R19") (pin "1") (pinfunction "1_1") (pintype "passive"))
      (node (ref "SD1") (pin "5") (pinfunction "CLK_5") (pintype "passive"))
    )
    (net (code "103") (name "Net-(SD1-CMD)") (class "Default")
      (node (ref "R19") (pin "4") (pinfunction "4_4") (pintype "passive"))
      (node (ref "SD1") (pin "2") (pinfunction "CMD_2") (pintype "passive"))
    )
    (net (code "104") (name "Net-(SD1-DAT0)") (class "Default")
      (node (ref "R19") (pin "3") (pinfunction "3_3") (pintype "passive"))
      (node (ref "SD1") (pin "7") (pinfunction "DAT0_7") (pintype "passive"))
    )
    (net (code "105") (name "Net-(SD1-DAT1)") (class "Default")
      (node (ref "R19") (pin "2") (pinfunction "2_2") (pintype "passive"))
      (node (ref "SD1") (pin "8") (pinfunction "DAT1_8") (pintype "passive"))
    )
    (net (code "106") (name "Net-(SD1-VSS1)") (class "Default")
      (node (ref "R31") (pin "2") (pinfunction "2_2") (pintype "passive"))
      (node (ref "SD1") (pin "3") (pinfunction "VSS1_3") (pintype "passive"))
    )
    (net (code "107") (name "Net-(U11-CLKB)") (class "Default")
      (node (ref "R19") (pin "8") (pinfunction "8_8") (pintype "passive"))
      (node (ref "U11") (pin "8") (pinfunction "CLKB_8") (pintype "output"))
    )
    (net (code "108") (name "Net-(U11-CMDB)") (class "Default")
      (node (ref "R31") (pin "7") (pinfunction "7_7") (pintype "passive"))
      (node (ref "U11") (pin "13") (pinfunction "CMDB_13") (pintype "bidirectional"))
    )
    (net (code "109") (name "Net-(U11-DAT0B)") (class "Default")
      (node (ref "R19") (pin "6") (pinfunction "6_6") (pintype "passive"))
      (node (ref "U11") (pin "10") (pinfunction "DAT0B_10") (pintype "bidirectional"))
    )
    (net (code "110") (name "Net-(U11-DAT1B)") (class "Default")
      (node (ref "R19") (pin "7") (pinfunction "7_7") (pintype "passive"))
      (node (ref "U11") (pin "9") (pinfunction "DAT1B_9") (pintype "bidirectional"))
    )
    (net (code "111") (name "Net-(U11-DAT2B)") (class "Default")
      (node (ref "R31") (pin "8") (pinfunction "8_8") (pintype "passive"))
      (node (ref "U11") (pin "12") (pinfunction "DAT2B_12") (pintype "bidirectional"))
    )
    (net (code "112") (name "Net-(U11-DAT3B)") (class "Default")
      (node (ref "R19") (pin "5") (pinfunction "5_5") (pintype "passive"))
      (node (ref "U11") (pin "11") (pinfunction "DAT3B_11") (pintype "bidirectional"))
    )
    (net (code "113") (name "Net-(U11-VCCB)") (class "Default")
      (node (ref "C39") (pin "2") (pinfunction "2_2") (pintype "passive"))
      (node (ref "U11") (pin "14") (pinfunction "VCCB_14") (pintype "power_in"))
      (node (ref "U16") (pin "B2") (pinfunction "VOUT_B2") (pintype "power_in"))
    )
    (net (code "114") (name "PL_1V8") (class "Default")
      (node (ref "C6") (pin "2") (pinfunction "2_2") (pintype "passive"))
      (node (ref "C7") (pin "2") (pinfunction "2_2") (pintype "passive"))
      (node (ref "SOM1") (pin "D01") (pinfunction "D01_D01") (pintype "passive"))
      (node (ref "SOM1") (pin "D02") (pinfunction "D02_D02") (pintype "passive"))
    )
    (net (code "115") (name "PL_3V3") (class "Default")
      (node (ref "C4") (pin "2") (pinfunction "2_2") (pintype "passive"))
      (node (ref "C40") (pin "2") (pinfunction "2_2") (pintype "passive"))
      (node (ref "C44") (pin "2") (pinfunction "2_2") (pintype "passive"))
      (node (ref "C5") (pin "2") (pinfunction "2_2") (pintype "passive"))
      (node (ref "C58") (pin "2") (pinfunction "2_2") (pintype "passive"))
      (node (ref "SD1") (pin "4") (pinfunction "VDD_4") (pintype "passive"))
      (node (ref "SOM1") (pin "B13") (pinfunction "B13_B13") (pintype "passive"))
      (node (ref "SOM1") (pin "B14") (pinfunction "B14_B14") (pintype "passive"))
      (node (ref "U16") (pin "A2") (pinfunction "VINA_A2") (pintype "input"))
    )
    (net (code "116") (name "PS_1V8") (class "Default")
      (node (ref "C57") (pin "2") (pinfunction "2_2") (pintype "passive"))
      (node (ref "C59") (pin "2") (pinfunction "2_2") (pintype "passive"))
      (node (ref "P1") (pin "13") (pinfunction "13_13") (pintype "passive"))
      (node (ref "R16") (pin "2") (pinfunction "2_2") (pintype "passive"))
      (node (ref "U11") (pin "15") (pinfunction "VCCA_15") (pintype "power_in"))
      (node (ref "U16") (pin "A1") (pinfunction "EN_A1") (pintype "input"))
      (node (ref "U16") (pin "C2") (pinfunction "VINB_C2") (pintype "power_in"))
    )
    (net (code "117") (name "SOM_5V0") (class "Default")
      (node (ref "C10") (pin "2") (pinfunction "2_2") (pintype "passive"))
      (node (ref "C11") (pin "2") (pinfunction "2_2") (pintype "passive"))
      (node (ref "C8") (pin "2") (pinfunction "2_2") (pintype "passive"))
      (node (ref "C9") (pin "2") (pinfunction "2_2") (pintype "passive"))
      (node (ref "SOM1") (pin "A59") (pinfunction "A59_A59") (pintype "passive"))
      (node (ref "SOM1") (pin "A60") (pinfunction "A60_A60") (pintype "passive"))
      (node (ref "SOM1") (pin "B60") (pinfunction "B60_B60") (pintype "passive"))
      (node (ref "SOM1") (pin "C59") (pinfunction "C59_C59") (pintype "passive"))
      (node (ref "SOM1") (pin "C60") (pinfunction "C60_C60") (pintype "passive"))
      (node (ref "SOM1") (pin "D60") (pinfunction "D60_D60") (pintype "passive"))
    )
    (net (code "118") (name "unconnected-(P1-Pad3)") (class "Default")
      (node (ref "P1") (pin "3") (pinfunction "3_3") (pintype "passive+no_connect"))
    )
    (net (code "119") (name "unconnected-(R31-Pad3)") (class "Default")
      (node (ref "R31") (pin "3") (pinfunction "3_3") (pintype "passive"))
    )
    (net (code "120") (name "unconnected-(R31-Pad4)") (class "Default")
      (node (ref "R31") (pin "4") (pinfunction "4_4") (pintype "passive"))
    )
    (net (code "121") (name "unconnected-(R31-Pad5)") (class "Default")
      (node (ref "R31") (pin "5") (pinfunction "5_5") (pintype "passive"))
    )
    (net (code "122") (name "unconnected-(R31-Pad6)") (class "Default")
      (node (ref "R31") (pin "6") (pinfunction "6_6") (pintype "passive"))
    )
    (net (code "123") (name "unconnected-(SOM1-PadA03)") (class "Default")
      (node (ref "SOM1") (pin "A03") (pinfunction "A03_A03") (pintype "passive"))
    )
    (net (code "124") (name "unconnected-(SOM1-PadA04)") (class "Default")
      (node (ref "SOM1") (pin "A04") (pinfunction "A04_A04") (pintype "passive"))
    )
    (net (code "125") (name "unconnected-(SOM1-PadA06)") (class "Default")
      (node (ref "SOM1") (pin "A06") (pinfunction "A06_A06") (pintype "passive"))
    )
    (net (code "126") (name "unconnected-(SOM1-PadA07)") (class "Default")
      (node (ref "SOM1") (pin "A07") (pinfunction "A07_A07") (pintype "passive"))
    )
    (net (code "127") (name "unconnected-(SOM1-PadA09)") (class "Default")
      (node (ref "SOM1") (pin "A09") (pinfunction "A09_A09") (pintype "passive"))
    )
    (net (code "128") (name "unconnected-(SOM1-PadA10)") (class "Default")
      (node (ref "SOM1") (pin "A10") (pinfunction "A10_A10") (pintype "passive"))
    )
    (net (code "129") (name "unconnected-(SOM1-PadA12)") (class "Default")
      (node (ref "SOM1") (pin "A12") (pinfunction "A12_A12") (pintype "passive"))
    )
    (net (code "130") (name "unconnected-(SOM1-PadA13)") (class "Default")
      (node (ref "SOM1") (pin "A13") (pinfunction "A13_A13") (pintype "passive"))
    )
    (net (code "131") (name "unconnected-(SOM1-PadA31)") (class "Default")
      (node (ref "SOM1") (pin "A31") (pinfunction "A31_A31") (pintype "passive"))
    )
    (net (code "132") (name "unconnected-(SOM1-PadA32)") (class "Default")
      (node (ref "SOM1") (pin "A32") (pinfunction "A32_A32") (pintype "passive"))
    )
    (net (code "133") (name "unconnected-(SOM1-PadA34)") (class "Default")
      (node (ref "SOM1") (pin "A34") (pinfunction "A34_A34") (pintype "passive"))
    )
    (net (code "134") (name "unconnected-(SOM1-PadA35)") (class "Default")
      (node (ref "SOM1") (pin "A35") (pinfunction "A35_A35") (pintype "passive"))
    )
    (net (code "135") (name "unconnected-(SOM1-PadA36)") (class "Default")
      (node (ref "SOM1") (pin "A36") (pinfunction "A36_A36") (pintype "passive"))
    )
    (net (code "136") (name "unconnected-(SOM1-PadA42)") (class "Default")
      (node (ref "SOM1") (pin "A42") (pinfunction "A42_A42") (pintype "passive"))
    )
    (net (code "137") (name "unconnected-(SOM1-PadA43)") (class "Default")
      (node (ref "SOM1") (pin "A43") (pinfunction "A43_A43") (pintype "passive"))
    )
    (net (code "138") (name "unconnected-(SOM1-PadA44)") (class "Default")
      (node (ref "SOM1") (pin "A44") (pinfunction "A44_A44") (pintype "passive"))
    )
    (net (code "139") (name "unconnected-(SOM1-PadA51)") (class "Default")
      (node (ref "SOM1") (pin "A51") (pinfunction "A51_A51") (pintype "passive"))
    )
    (net (code "140") (name "unconnected-(SOM1-PadA52)") (class "Default")
      (node (ref "SOM1") (pin "A52") (pinfunction "A52_A52") (pintype "passive"))
    )
    (net (code "141") (name "unconnected-(SOM1-PadA55)") (class "Default")
      (node (ref "SOM1") (pin "A55") (pinfunction "A55_A55") (pintype "passive"))
    )
    (net (code "142") (name "unconnected-(SOM1-PadA56)") (class "Default")
      (node (ref "SOM1") (pin "A56") (pinfunction "A56_A56") (pintype "passive"))
    )
    (net (code "143") (name "unconnected-(SOM1-PadB01)") (class "Default")
      (node (ref "SOM1") (pin "B01") (pinfunction "B01_B01") (pintype "passive"))
    )
    (net (code "144") (name "unconnected-(SOM1-PadB02)") (class "Default")
      (node (ref "SOM1") (pin "B02") (pinfunction "B02_B02") (pintype "passive"))
    )
    (net (code "145") (name "unconnected-(SOM1-PadB04)") (class "Default")
      (node (ref "SOM1") (pin "B04") (pinfunction "B04_B04") (pintype "passive"))
    )
    (net (code "146") (name "unconnected-(SOM1-PadB05)") (class "Default")
      (node (ref "SOM1") (pin "B05") (pinfunction "B05_B05") (pintype "passive"))
    )
    (net (code "147") (name "unconnected-(SOM1-PadB07)") (class "Default")
      (node (ref "SOM1") (pin "B07") (pinfunction "B07_B07") (pintype "passive"))
    )
    (net (code "148") (name "unconnected-(SOM1-PadB08)") (class "Default")
      (node (ref "SOM1") (pin "B08") (pinfunction "B08_B08") (pintype "passive"))
    )
    (net (code "149") (name "unconnected-(SOM1-PadB10)") (class "Default")
      (node (ref "SOM1") (pin "B10") (pinfunction "B10_B10") (pintype "passive"))
    )
    (net (code "150") (name "unconnected-(SOM1-PadB11)") (class "Default")
      (node (ref "SOM1") (pin "B11") (pinfunction "B11_B11") (pintype "passive"))
    )
    (net (code "151") (name "unconnected-(SOM1-PadB24)") (class "Default")
      (node (ref "SOM1") (pin "B24") (pinfunction "B24_B24") (pintype "passive"))
    )
    (net (code "152") (name "unconnected-(SOM1-PadB25)") (class "Default")
      (node (ref "SOM1") (pin "B25") (pinfunction "B25_B25") (pintype "passive"))
    )
    (net (code "153") (name "unconnected-(SOM1-PadB28)") (class "Default")
      (node (ref "SOM1") (pin "B28") (pinfunction "B28_B28") (pintype "passive"))
    )
    (net (code "154") (name "unconnected-(SOM1-PadB32)") (class "Default")
      (node (ref "SOM1") (pin "B32") (pinfunction "B32_B32") (pintype "passive"))
    )
    (net (code "155") (name "unconnected-(SOM1-PadB34)") (class "Default")
      (node (ref "SOM1") (pin "B34") (pinfunction "B34_B34") (pintype "passive"))
    )
    (net (code "156") (name "unconnected-(SOM1-PadB38)") (class "Default")
      (node (ref "SOM1") (pin "B38") (pinfunction "B38_B38") (pintype "passive"))
    )
    (net (code "157") (name "unconnected-(SOM1-PadB44)") (class "Default")
      (node (ref "SOM1") (pin "B44") (pinfunction "B44_B44") (pintype "passive"))
    )
    (net (code "158") (name "unconnected-(SOM1-PadB45)") (class "Default")
      (node (ref "SOM1") (pin "B45") (pinfunction "B45_B45") (pintype "passive"))
    )
    (net (code "159") (name "unconnected-(SOM1-PadB46)") (class "Default")
      (node (ref "SOM1") (pin "B46") (pinfunction "B46_B46") (pintype "passive"))
    )
    (net (code "160") (name "unconnected-(SOM1-PadB57)") (class "Default")
      (node (ref "SOM1") (pin "B57") (pinfunction "B57_B57") (pintype "passive"))
    )
    (net (code "161") (name "unconnected-(SOM1-PadB58)") (class "Default")
      (node (ref "SOM1") (pin "B58") (pinfunction "B58_B58") (pintype "passive"))
    )
    (net (code "162") (name "unconnected-(SOM1-PadC03)") (class "Default")
      (node (ref "SOM1") (pin "C03") (pinfunction "C03_C03") (pintype "passive"))
    )
    (net (code "163") (name "unconnected-(SOM1-PadC04)") (class "Default")
      (node (ref "SOM1") (pin "C04") (pinfunction "C04_C04") (pintype "passive"))
    )
    (net (code "164") (name "unconnected-(SOM1-PadC06)") (class "Default")
      (node (ref "SOM1") (pin "C06") (pinfunction "C06_C06") (pintype "passive"))
    )
    (net (code "165") (name "unconnected-(SOM1-PadC07)") (class "Default")
      (node (ref "SOM1") (pin "C07") (pinfunction "C07_C07") (pintype "passive"))
    )
    (net (code "166") (name "unconnected-(SOM1-PadC09)") (class "Default")
      (node (ref "SOM1") (pin "C09") (pinfunction "C09_C09") (pintype "passive"))
    )
    (net (code "167") (name "unconnected-(SOM1-PadC10)") (class "Default")
      (node (ref "SOM1") (pin "C10") (pinfunction "C10_C10") (pintype "passive"))
    )
    (net (code "168") (name "unconnected-(SOM1-PadC12)") (class "Default")
      (node (ref "SOM1") (pin "C12") (pinfunction "C12_C12") (pintype "passive"))
    )
    (net (code "169") (name "unconnected-(SOM1-PadC13)") (class "Default")
      (node (ref "SOM1") (pin "C13") (pinfunction "C13_C13") (pintype "passive"))
    )
    (net (code "170") (name "unconnected-(SOM1-PadC42)") (class "Default")
      (node (ref "SOM1") (pin "C42") (pinfunction "C42_C42") (pintype "passive"))
    )
    (net (code "171") (name "unconnected-(SOM1-PadC43)") (class "Default")
      (node (ref "SOM1") (pin "C43") (pinfunction "C43_C43") (pintype "passive"))
    )
    (net (code "172") (name "unconnected-(SOM1-PadC44)") (class "Default")
      (node (ref "SOM1") (pin "C44") (pinfunction "C44_C44") (pintype "passive"))
    )
    (net (code "173") (name "unconnected-(SOM1-PadC45)") (class "Default")
      (node (ref "SOM1") (pin "C45") (pinfunction "C45_C45") (pintype "passive"))
    )
    (net (code "174") (name "unconnected-(SOM1-PadC47)") (class "Default")
      (node (ref "SOM1") (pin "C47") (pinfunction "C47_C47") (pintype "passive"))
    )
    (net (code "175") (name "unconnected-(SOM1-PadC48)") (class "Default")
      (node (ref "SOM1") (pin "C48") (pinfunction "C48_C48") (pintype "passive"))
    )
    (net (code "176") (name "unconnected-(SOM1-PadC51)") (class "Default")
      (node (ref "SOM1") (pin "C51") (pinfunction "C51_C51") (pintype "passive"))
    )
    (net (code "177") (name "unconnected-(SOM1-PadC52)") (class "Default")
      (node (ref "SOM1") (pin "C52") (pinfunction "C52_C52") (pintype "passive"))
    )
    (net (code "178") (name "unconnected-(SOM1-PadC55)") (class "Default")
      (node (ref "SOM1") (pin "C55") (pinfunction "C55_C55") (pintype "passive"))
    )
    (net (code "179") (name "unconnected-(SOM1-PadC56)") (class "Default")
      (node (ref "SOM1") (pin "C56") (pinfunction "C56_C56") (pintype "passive"))
    )
    (net (code "180") (name "unconnected-(SOM1-PadD04)") (class "Default")
      (node (ref "SOM1") (pin "D04") (pinfunction "D04_D04") (pintype "passive"))
    )
    (net (code "181") (name "unconnected-(SOM1-PadD05)") (class "Default")
      (node (ref "SOM1") (pin "D05") (pinfunction "D05_D05") (pintype "passive"))
    )
    (net (code "182") (name "unconnected-(SOM1-PadD07)") (class "Default")
      (node (ref "SOM1") (pin "D07") (pinfunction "D07_D07") (pintype "passive"))
    )
    (net (code "183") (name "unconnected-(SOM1-PadD08)") (class "Default")
      (node (ref "SOM1") (pin "D08") (pinfunction "D08_D08") (pintype "passive"))
    )
    (net (code "184") (name "unconnected-(SOM1-PadD10)") (class "Default")
      (node (ref "SOM1") (pin "D10") (pinfunction "D10_D10") (pintype "passive"))
    )
    (net (code "185") (name "unconnected-(SOM1-PadD11)") (class "Default")
      (node (ref "SOM1") (pin "D11") (pinfunction "D11_D11") (pintype "passive"))
    )
    (net (code "186") (name "unconnected-(SOM1-PadD13)") (class "Default")
      (node (ref "SOM1") (pin "D13") (pinfunction "D13_D13") (pintype "passive"))
    )
    (net (code "187") (name "unconnected-(SOM1-PadD14)") (class "Default")
      (node (ref "SOM1") (pin "D14") (pinfunction "D14_D14") (pintype "passive"))
    )
    (net (code "188") (name "unconnected-(SOM1-PadD28)") (class "Default")
      (node (ref "SOM1") (pin "D28") (pinfunction "D28_D28") (pintype "passive"))
    )
    (net (code "189") (name "unconnected-(SOM1-PadD32)") (class "Default")
      (node (ref "SOM1") (pin "D32") (pinfunction "D32_D32") (pintype "passive"))
    )
    (net (code "190") (name "unconnected-(SOM1-PadD40)") (class "Default")
      (node (ref "SOM1") (pin "D40") (pinfunction "D40_D40") (pintype "passive"))
    )
    (net (code "191") (name "unconnected-(SOM1-PadD41)") (class "Default")
      (node (ref "SOM1") (pin "D41") (pinfunction "D41_D41") (pintype "passive"))
    )
    (net (code "192") (name "unconnected-(SOM1-PadD42)") (class "Default")
      (node (ref "SOM1") (pin "D42") (pinfunction "D42_D42") (pintype "passive"))
    )
    (net (code "193") (name "unconnected-(SOM1-PadD45)") (class "Default")
      (node (ref "SOM1") (pin "D45") (pinfunction "D45_D45") (pintype "passive"))
    )
    (net (code "194") (name "unconnected-(SOM1-PadD46)") (class "Default")
      (node (ref "SOM1") (pin "D46") (pinfunction "D46_D46") (pintype "passive"))
    )
    (net (code "195") (name "unconnected-(SOM1-PadD49)") (class "Default")
      (node (ref "SOM1") (pin "D49") (pinfunction "D49_D49") (pintype "passive"))
    )
    (net (code "196") (name "unconnected-(SOM1-PadD50)") (class "Default")
      (node (ref "SOM1") (pin "D50") (pinfunction "D50_D50") (pintype "passive"))
    )
    (net (code "197") (name "unconnected-(U11-CLK_FB-Pad6)") (class "Default")
      (node (ref "U11") (pin "6") (pinfunction "CLK_FB_6") (pintype "output"))
    )
  )
)
